# VREG_AOZ1021AI_4V2_3A.net
KiCad netlist of a schematic drawn in Altium Designer
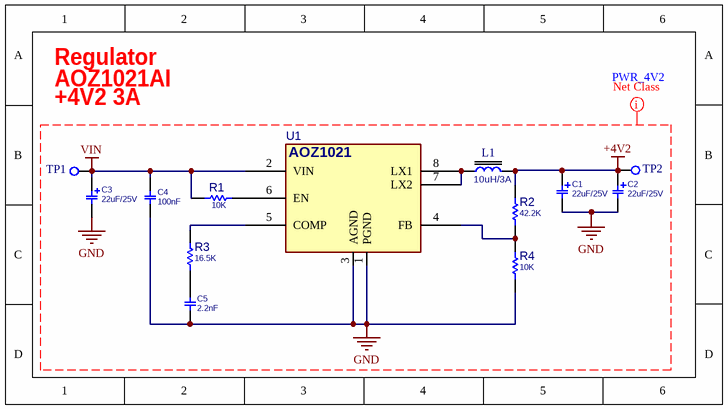
[diagram p0: VREG AOZ1021AI +4V2 3A.SchDoc]

(export (version "E")
  (design (tool "Eeschema 10.0.6"))
  (components
    (comp (ref "C1")
      (value "22uF/25V")
      (footprint "C_TN_A")
      (description "CAP, SMD, TAN")
      (libsource (lib "Passive") (part "CAP_SMD_TAN"))
    )
    (comp (ref "C2")
      (value "22uF/25V")
      (footprint "C_TN_A")
      (description "CAP, SMD, TAN")
      (libsource (lib "Passive") (part "CAP_SMD_TAN"))
    )
    (comp (ref "C3")
      (value "22uF/25V")
      (footprint "C_TN_A")
      (description "CAP, SMD, TAN")
      (libsource (lib "Passive") (part "CAP_SMD_TAN"))
    )
    (comp (ref "C4")
      (value "100nF")
      (footprint "C0603S")
      (description "CAP, SMD, MLCC")
      (fields (field (name "MANF_P#") "MANF_PART#") (field (name "MANF") "Murata"))
      (libsource (lib "Passive") (part "CAP_SMD_MLCC"))
    )
    (comp (ref "C5")
      (value "2.2nF")
      (footprint "C0603S")
      (description "CAP, SMD, MLCC")
      (fields (field (name "MANF_P#") "MANF_PART#") (field (name "MANF") "Murata"))
      (libsource (lib "Passive") (part "CAP_SMD_MLCC"))
    )
    (comp (ref "L1")
      (value "10uH/3A")
      (footprint "L_8X8")
      (description "IND, PWR, SMD")
      (libsource (lib "Passive") (part "INDPWR_SMD"))
    )
    (comp (ref "R1")
      (value "10K")
      (footprint "R0603S")
      (description "RES, SMD")
      (fields (field (name "MANF_P#") "RK73H1ETTP4701F") (field (name "MANF") "KOA SPEER"))
      (libsource (lib "Passive") (part "RES_SMD"))
    )
    (comp (ref "R2")
      (value "42.2K")
      (footprint "R0603S")
      (description "RES, SMD")
      (fields (field (name "MANF_P#") "RK73H1ETTP4701F") (field (name "MANF") "KOA SPEER"))
      (libsource (lib "Passive") (part "RES_SMD"))
    )
    (comp (ref "R3")
      (value "16.5K")
      (footprint "R0603S")
      (description "RES, SMD")
      (fields (field (name "MANF_P#") "RK73H1ETTP4701F") (field (name "MANF") "KOA SPEER"))
      (libsource (lib "Passive") (part "RES_SMD"))
    )
    (comp (ref "R4")
      (value "10K")
      (footprint "R0603S")
      (description "RES, SMD")
      (fields (field (name "MANF_P#") "RK73H1ETTP4701F") (field (name "MANF") "KOA SPEER"))
      (libsource (lib "Passive") (part "RES_SMD"))
    )
    (comp (ref "TP1")
      (value "Test Point")
      (footprint "TPSMD_C1")
      (libsource (lib "PW Components") (part "Test Point"))
    )
    (comp (ref "TP2")
      (value "Test Point")
      (footprint "TPSMD_C1")
      (libsource (lib "PW Components") (part "Test Point"))
    )
    (comp (ref "U1")
      (value "AOZ1021AI")
      (footprint "SO_8")
      (description "REG, Switching, Buck, 3A, ADJ, 500KHz, 4.5~16VIN, SO-8")
      (fields (field (name "MANF") "AOSMD"))
      (libsource (lib "PW Components") (part "VREG_AOZ1021AI_SO8"))
    )
  )
  (nets
    (net (code "1") (name "+4V2") (class "Default")
      (node (ref "C1") (pin "1") (pinfunction "1_1") (pintype "passive"))
      (node (ref "C2") (pin "1") (pinfunction "1_1") (pintype "passive"))
      (node (ref "L1") (pin "2") (pinfunction "2_2") (pintype "passive"))
      (node (ref "R2") (pin "1") (pinfunction "1_1") (pintype "passive"))
      (node (ref "TP2") (pin "1") (pinfunction "TP_1") (pintype "passive"))
    )
    (net (code "2") (name "GND") (class "Default")
      (node (ref "C1") (pin "2") (pinfunction "2_2") (pintype "passive"))
      (node (ref "C2") (pin "2") (pinfunction "2_2") (pintype "passive"))
      (node (ref "C3") (pin "2") (pinfunction "2_2") (pintype "passive"))
      (node (ref "C4") (pin "1") (pinfunction "1_1") (pintype "passive"))
      (node (ref "C5") (pin "1") (pinfunction "1_1") (pintype "passive"))
      (node (ref "R4") (pin "2") (pinfunction "2_2") (pintype "passive"))
      (node (ref "U1") (pin "1") (pinfunction "PGND_1") (pintype "power_in"))
      (node (ref "U1") (pin "3") (pinfunction "AGND_3") (pintype "power_in"))
    )
    (net (code "3") (name "Net-(C5-Pad2)") (class "Default")
      (node (ref "C5") (pin "2") (pinfunction "2_2") (pintype "passive"))
      (node (ref "R3") (pin "2") (pinfunction "2_2") (pintype "passive"))
    )
    (net (code "4") (name "Net-(U1-COMP)") (class "Default")
      (node (ref "R3") (pin "1") (pinfunction "1_1") (pintype "passive"))
      (node (ref "U1") (pin "5") (pinfunction "COMP_5") (pintype "passive"))
    )
    (net (code "5") (name "Net-(U1-EN)") (class "Default")
      (node (ref "R1") (pin "1") (pinfunction "1_1") (pintype "passive"))
      (node (ref "U1") (pin "6") (pinfunction "EN_6") (pintype "passive"))
    )
    (net (code "6") (name "Net-(U1-FB)") (class "Default")
      (node (ref "R2") (pin "2") (pinfunction "2_2") (pintype "passive"))
      (node (ref "R4") (pin "1") (pinfunction "1_1") (pintype "passive"))
      (node (ref "U1") (pin "4") (pinfunction "FB_4") (pintype "passive"))
    )
    (net (code "7") (name "Net-(U1-LX1)") (class "Default")
      (node (ref "L1") (pin "1") (pinfunction "1_1") (pintype "passive"))
      (node (ref "U1") (pin "7") (pinfunction "LX2_7") (pintype "passive"))
      (node (ref "U1") (pin "8") (pinfunction "LX1_8") (pintype "passive"))
    )
    (net (code "8") (name "VIN") (class "Default")
      (node (ref "C3") (pin "1") (pinfunction "1_1") (pintype "passive"))
      (node (ref "C4") (pin "2") (pinfunction "2_2") (pintype "passive"))
      (node (ref "R1") (pin "2") (pinfunction "2_2") (pintype "passive"))
      (node (ref "TP1") (pin "1") (pinfunction "TP_1") (pintype "passive"))
      (node (ref "U1") (pin "2") (pinfunction "VIN_2") (pintype "power_in"))
    )
  )
)
